# napajeniMOB.net
KiCad netlist of a schematic drawn in EAGLE
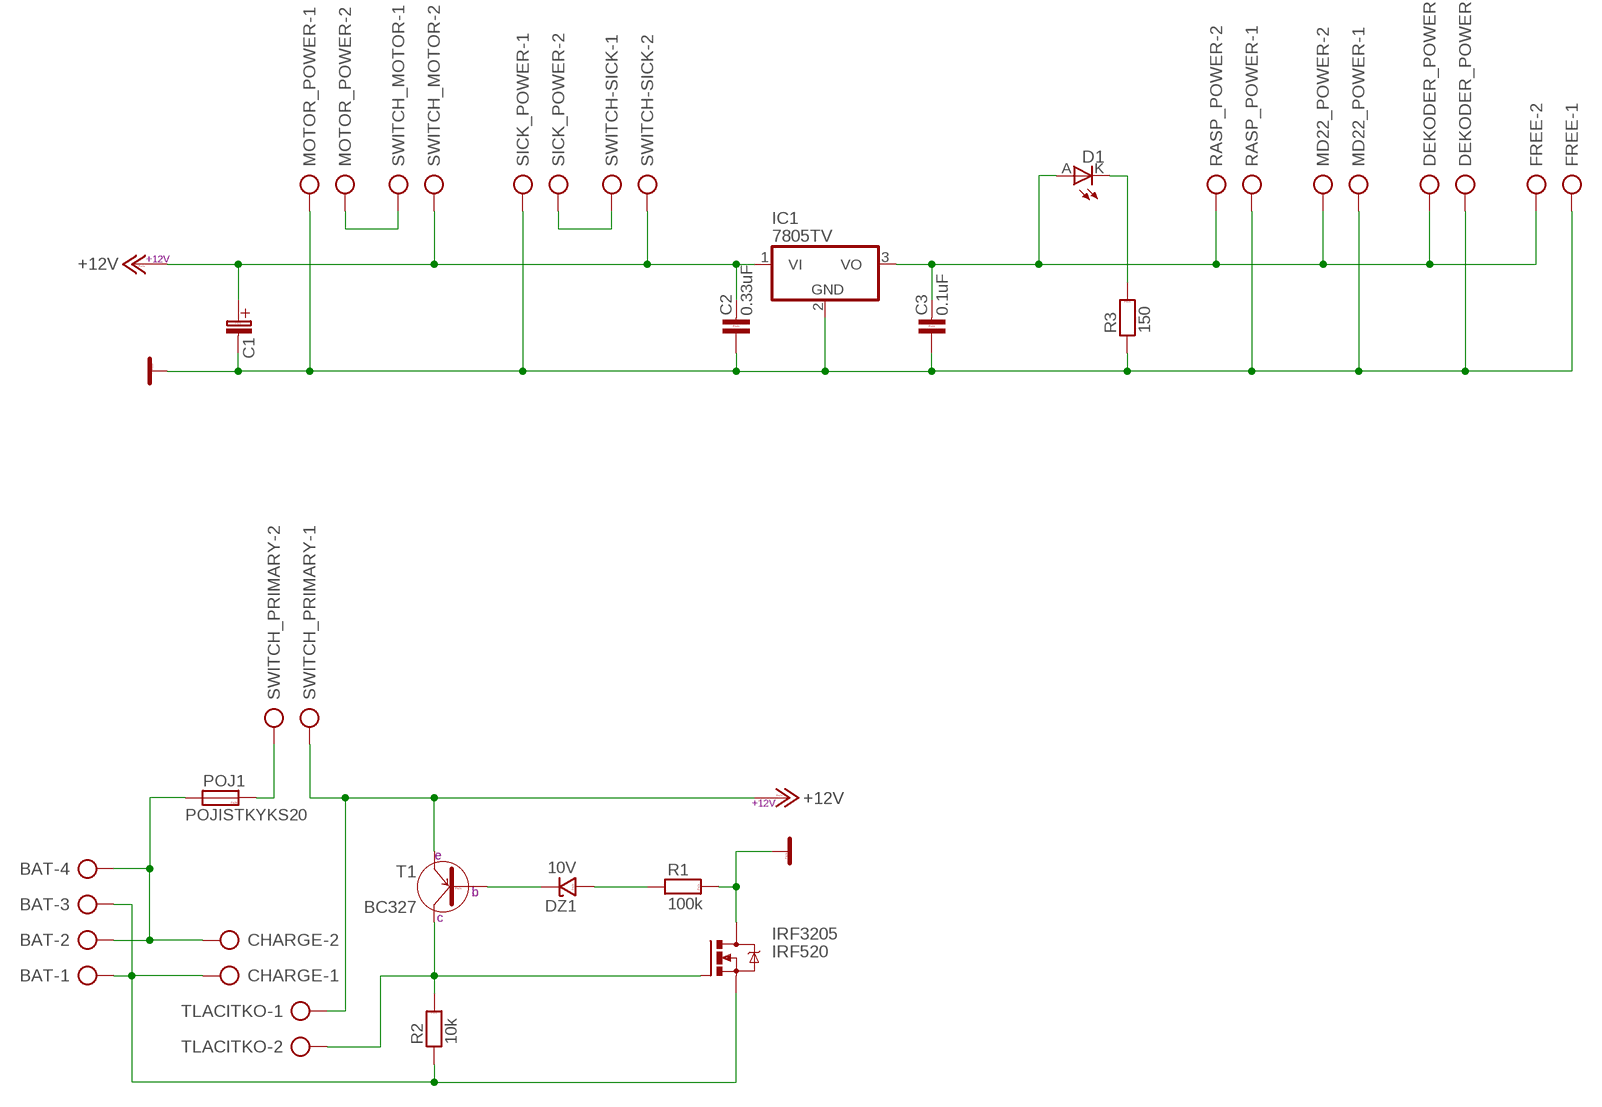
[diagram p0: schematic, sheet 1]

(export (version "E")
  (design (tool "Eeschema 10.0.6"))
  (components
    (comp (ref "BAT")
      (value "AK500/4")
      (footprint "eagle-import:AK500_4")
      (libsource (lib "eagle-import") (part "AK500/4"))
    )
    (comp (ref "C1")
      (value "C-ELEKTROLYT_7,5+")
      (footprint "eagle-import:C-EL7,5+")
      (libsource (lib "eagle-import") (part "C-ELEKTROLYT_7,5+"))
    )
    (comp (ref "C2")
      (value "0.33uF")
      (footprint "eagle-import:C-5")
      (libsource (lib "eagle-import") (part "C-KERAMIK_5"))
    )
    (comp (ref "C3")
      (value "0.1uF")
      (footprint "eagle-import:C-5")
      (libsource (lib "eagle-import") (part "C-KERAMIK_5"))
    )
    (comp (ref "CHARGE")
      (value "AK500/2")
      (footprint "eagle-import:AK500_2")
      (libsource (lib "eagle-import") (part "AK500/2"))
    )
    (comp (ref "D1")
      (value "LEDLED5MM")
      (footprint "eagle-import:LED5MM")
      (libsource (lib "eagle-import") (part "LEDLED5MM"))
    )
    (comp (ref "DEKODER_POWER")
      (value "AK500/2")
      (footprint "eagle-import:AK500_2")
      (libsource (lib "eagle-import") (part "AK500/2"))
    )
    (comp (ref "DZ1")
      (value "10V")
      (footprint "eagle-import:DO41")
      (libsource (lib "eagle-import") (part "D-ZENEROVA_2W_BZY"))
    )
    (comp (ref "FREE")
      (value "AK500/2")
      (footprint "eagle-import:AK500_2")
      (libsource (lib "eagle-import") (part "AK500/2"))
    )
    (comp (ref "IC1")
      (value "7805TV")
      (footprint "eagle-import:TO220V")
      (libsource (lib "eagle-import") (part "78TV05"))
    )
    (comp (ref "IRF3205")
      (value "IRF520")
      (footprint "eagle-import:TO220BV")
      (libsource (lib "eagle-import") (part "IRF520"))
    )
    (comp (ref "MD22_POWER")
      (value "AK500/2")
      (footprint "eagle-import:AK500_2")
      (libsource (lib "eagle-import") (part "AK500/2"))
    )
    (comp (ref "MOTOR_POWER")
      (value "AK500/2")
      (footprint "eagle-import:AK500_2")
      (libsource (lib "eagle-import") (part "AK500/2"))
    )
    (comp (ref "POJ1")
      (value "POJISTKYKS20")
      (footprint "eagle-import:POJ_KS20")
      (libsource (lib "eagle-import") (part "POJISTKYKS20"))
    )
    (comp (ref "R1")
      (value "100k")
      (footprint "eagle-import:R-10")
      (libsource (lib "eagle-import") (part "R_10"))
    )
    (comp (ref "R2")
      (value "10k")
      (footprint "eagle-import:R-10")
      (libsource (lib "eagle-import") (part "R_10"))
    )
    (comp (ref "R3")
      (value "150")
      (footprint "eagle-import:R-10")
      (libsource (lib "eagle-import") (part "R_10"))
    )
    (comp (ref "RASP_POWER")
      (value "AK500/2")
      (footprint "eagle-import:AK500_2")
      (libsource (lib "eagle-import") (part "AK500/2"))
    )
    (comp (ref "SICK_POWER")
      (value "AK500/2")
      (footprint "eagle-import:AK500_2")
      (libsource (lib "eagle-import") (part "AK500/2"))
    )
    (comp (ref "SWITCH-SICK")
      (value "AK500/2")
      (footprint "eagle-import:AK500_2")
      (libsource (lib "eagle-import") (part "AK500/2"))
    )
    (comp (ref "SWITCH_MOTOR")
      (value "AK500/2")
      (footprint "eagle-import:AK500_2")
      (libsource (lib "eagle-import") (part "AK500/2"))
    )
    (comp (ref "SWITCH_PRIMARY")
      (value "AK500/2")
      (footprint "eagle-import:AK500_2")
      (libsource (lib "eagle-import") (part "AK500/2"))
    )
    (comp (ref "T1")
      (value "BC327")
      (footprint "eagle-import:TO-92")
      (libsource (lib "eagle-import") (part "BC327"))
    )
    (comp (ref "TLACITKO")
      (value "AK500/2")
      (footprint "eagle-import:AK500_2")
      (libsource (lib "eagle-import") (part "AK500/2"))
    )
  )
  (nets
    (net (code "1") (name "+12V") (class "Default")
      (node (ref "C1") (pin "C+") (pinfunction "C_EL+_C+") (pintype "passive"))
      (node (ref "C2") (pin "2") (pinfunction "2_2") (pintype "passive"))
      (node (ref "IC1") (pin "1") (pinfunction "VI_1") (pintype "input"))
      (node (ref "SWITCH-SICK") (pin "2") (pinfunction "KL_2") (pintype "passive"))
      (node (ref "SWITCH_MOTOR") (pin "2") (pinfunction "KL_2") (pintype "passive"))
      (node (ref "SWITCH_PRIMARY") (pin "1") (pinfunction "KL_1") (pintype "passive"))
      (node (ref "T1") (pin "3") (pinfunction "E_3") (pintype "passive"))
      (node (ref "TLACITKO") (pin "1") (pinfunction "KL_1") (pintype "passive"))
    )
    (net (code "2") (name "GND") (class "Default")
      (node (ref "C1") (pin "C-") (pinfunction "C_EL-_C-") (pintype "passive"))
      (node (ref "C2") (pin "1") (pinfunction "1_1") (pintype "passive"))
      (node (ref "C3") (pin "1") (pinfunction "1_1") (pintype "passive"))
      (node (ref "DEKODER_POWER") (pin "1") (pinfunction "KL_1") (pintype "passive"))
      (node (ref "FREE") (pin "1") (pinfunction "KL_1") (pintype "passive"))
      (node (ref "IC1") (pin "2") (pinfunction "GND_2") (pintype "passive"))
      (node (ref "IRF3205") (pin "D") (pinfunction "D_D") (pintype "passive"))
      (node (ref "MD22_POWER") (pin "1") (pinfunction "KL_1") (pintype "passive"))
      (node (ref "MOTOR_POWER") (pin "1") (pinfunction "KL_1") (pintype "passive"))
      (node (ref "R1") (pin "2") (pinfunction "2_2") (pintype "passive"))
      (node (ref "R3") (pin "1") (pinfunction "1_1") (pintype "passive"))
      (node (ref "RASP_POWER") (pin "1") (pinfunction "KL_1") (pintype "passive"))
      (node (ref "SICK_POWER") (pin "1") (pinfunction "KL_1") (pintype "passive"))
    )
    (net (code "3") (name "Net-(BATA-KL)") (class "Default")
      (node (ref "BAT") (pin "1") (pinfunction "KL_1") (pintype "passive"))
      (node (ref "BAT") (pin "3") (pinfunction "KL_3") (pintype "passive"))
      (node (ref "CHARGE") (pin "1") (pinfunction "KL_1") (pintype "passive"))
      (node (ref "IRF3205") (pin "S") (pinfunction "S_S") (pintype "passive"))
      (node (ref "R2") (pin "1") (pinfunction "1_1") (pintype "passive"))
    )
    (net (code "4") (name "Net-(BATB-KL)") (class "Default")
      (node (ref "BAT") (pin "2") (pinfunction "KL_2") (pintype "passive"))
      (node (ref "BAT") (pin "4") (pinfunction "KL_4") (pintype "passive"))
      (node (ref "CHARGE") (pin "2") (pinfunction "KL_2") (pintype "passive"))
      (node (ref "POJ1") (pin "1") (pinfunction "1_1") (pintype "passive"))
    )
    (net (code "5") (name "Net-(D1-C)") (class "Default")
      (node (ref "D1") (pin "K") (pinfunction "C_K") (pintype "passive"))
      (node (ref "R3") (pin "2") (pinfunction "2_2") (pintype "passive"))
    )
    (net (code "6") (name "Net-(DEKODER_POWERB-KL)") (class "Default")
      (node (ref "C3") (pin "2") (pinfunction "2_2") (pintype "passive"))
      (node (ref "D1") (pin "A") (pinfunction "A_A") (pintype "passive"))
      (node (ref "DEKODER_POWER") (pin "2") (pinfunction "KL_2") (pintype "passive"))
      (node (ref "FREE") (pin "2") (pinfunction "KL_2") (pintype "passive"))
      (node (ref "IC1") (pin "3") (pinfunction "VO_3") (pintype "passive"))
      (node (ref "MD22_POWER") (pin "2") (pinfunction "KL_2") (pintype "passive"))
      (node (ref "RASP_POWER") (pin "2") (pinfunction "KL_2") (pintype "passive"))
    )
    (net (code "7") (name "Net-(DZ1-PadA)") (class "Default")
      (node (ref "DZ1") (pin "A") (pinfunction "A_A") (pintype "passive"))
      (node (ref "R1") (pin "1") (pinfunction "1_1") (pintype "passive"))
    )
    (net (code "8") (name "Net-(MOTOR_POWERB-KL)") (class "Default")
      (node (ref "MOTOR_POWER") (pin "2") (pinfunction "KL_2") (pintype "passive"))
      (node (ref "SWITCH_MOTOR") (pin "1") (pinfunction "KL_1") (pintype "passive"))
    )
    (net (code "9") (name "Net-(SICK_POWERB-KL)") (class "Default")
      (node (ref "SICK_POWER") (pin "2") (pinfunction "KL_2") (pintype "passive"))
      (node (ref "SWITCH-SICK") (pin "1") (pinfunction "KL_1") (pintype "passive"))
    )
    (net (code "10") (name "Net-(SWITCH_PRIMARYB-KL)") (class "Default")
      (node (ref "POJ1") (pin "2") (pinfunction "2_2") (pintype "passive"))
      (node (ref "SWITCH_PRIMARY") (pin "2") (pinfunction "KL_2") (pintype "passive"))
    )
    (net (code "11") (name "Net-(T1-B)") (class "Default")
      (node (ref "DZ1") (pin "K") (pinfunction "K_K") (pintype "passive"))
      (node (ref "T1") (pin "2") (pinfunction "B_2") (pintype "passive"))
    )
    (net (code "12") (name "Net-(T1-C)") (class "Default")
      (node (ref "IRF3205") (pin "G") (pinfunction "G_G") (pintype "passive"))
      (node (ref "R2") (pin "2") (pinfunction "2_2") (pintype "passive"))
      (node (ref "T1") (pin "1") (pinfunction "C_1") (pintype "passive"))
      (node (ref "TLACITKO") (pin "2") (pinfunction "KL_2") (pintype "passive"))
    )
  )
)
